# DC_DC_5V_2.net
KiCad netlist of a schematic drawn in Altium Designer
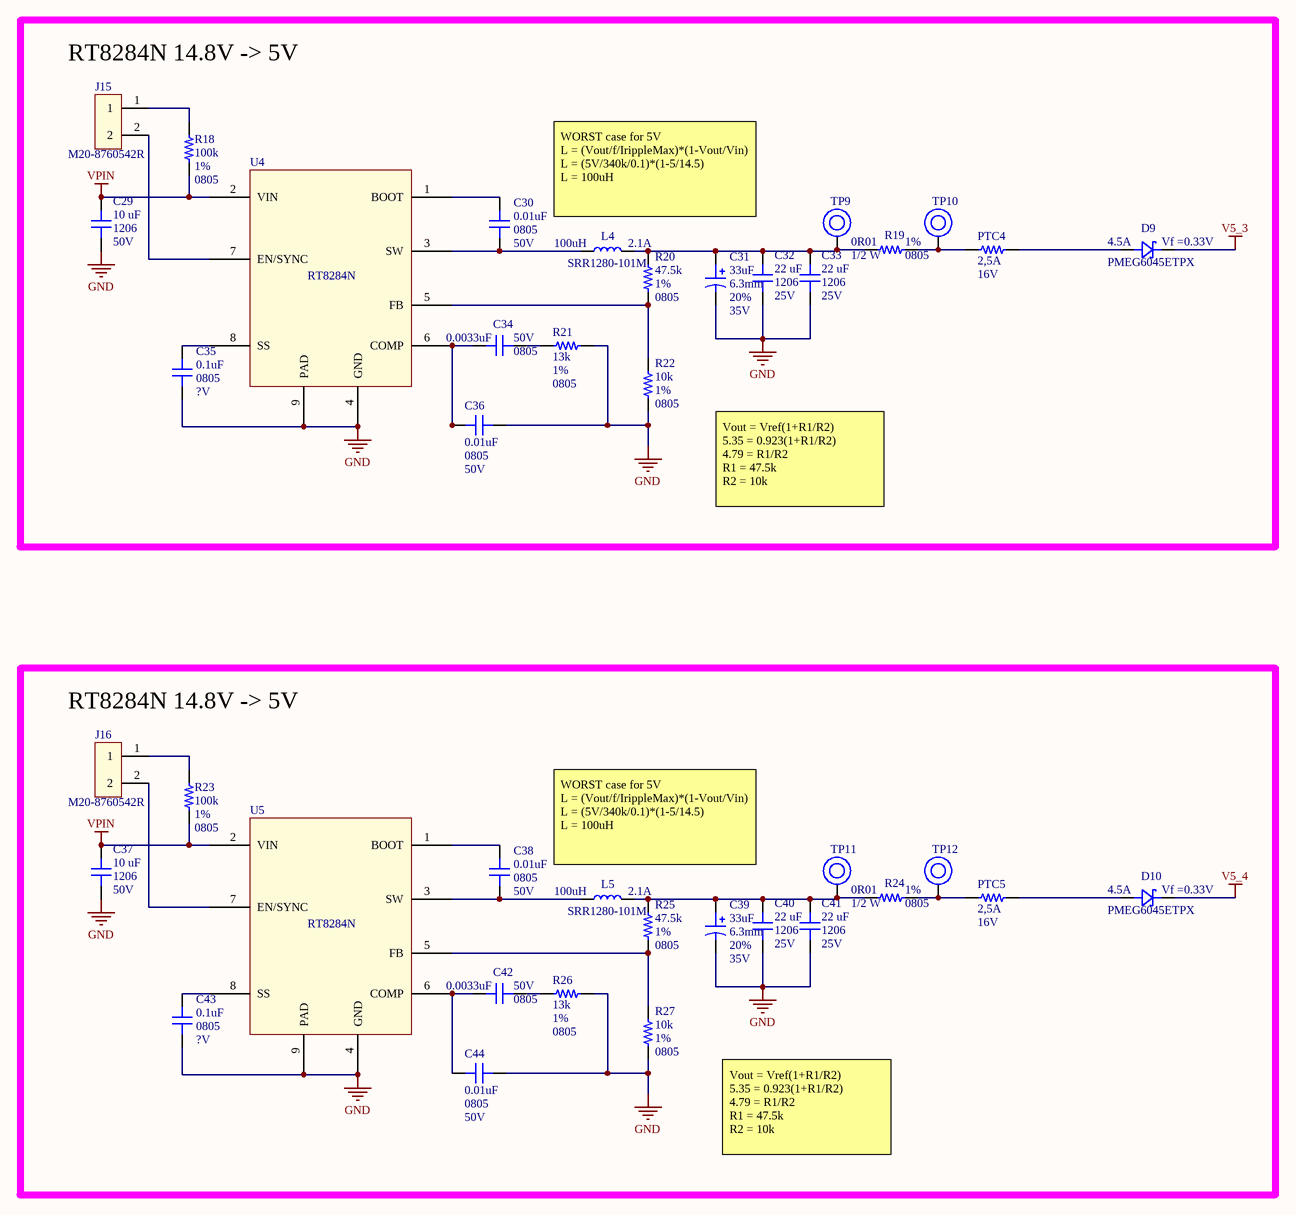
[diagram p0: DC_DC_5V_2.SchDoc]

(export (version "E")
  (design (tool "Eeschema 10.0.6"))
  (components
    (comp (ref "C29")
      (value "10 uF")
      (footprint "CAP_1206")
      (description "CAP - 1206")
      (fields
        (field (name "PACKAGE") "1206")
        (field (name "VOLTAGE") "50V")
        (field (name "PART NUMBER") "GRT31CR61H106ME01L")
      )
      (libsource (lib "SecureBot") (part "CAP - 1206"))
    )
    (comp (ref "C30")
      (value "0.01uF")
      (footprint "CAP_0805")
      (description "CAP - 0805")
      (fields
        (field (name "PART NUMBER") "CL21B103KBANNNC")
        (field (name "PACKAGE") "0805")
        (field (name "VOLTAGE") "50V")
      )
      (libsource (lib "SecureBot") (part "CAP - 0805"))
    )
    (comp (ref "C31")
      (value "33uF")
      (footprint "CAP ALU - 6.3mm DIA")
      (description "CAP ALU - 6.3mm")
      (fields
        (field (name "PACKAGE") "6.3mm")
        (field (name "TOLERANCE") "20%")
        (field (name "VOLTAGE") "35V")
        (field (name "PART NUMBER") "EEE-FK1V330P")
      )
      (libsource (lib "SecureBot") (part "CAP ALU - 6_3mm"))
    )
    (comp (ref "C32")
      (value "22 uF")
      (footprint "CAP_1206")
      (description "CAP - 1206")
      (fields
        (field (name "PACKAGE") "1206")
        (field (name "VOLTAGE") "25V")
        (field (name "PART NUMBER") "CL31A226KAHNNNE")
      )
      (libsource (lib "SecureBot") (part "CAP - 1206"))
    )
    (comp (ref "C33")
      (value "22 uF")
      (footprint "CAP_1206")
      (description "CAP - 1206")
      (fields
        (field (name "PACKAGE") "1206")
        (field (name "VOLTAGE") "25V")
        (field (name "PART NUMBER") "CL31A226KAHNNNE")
      )
      (libsource (lib "SecureBot") (part "CAP - 1206"))
    )
    (comp (ref "C34")
      (value "0.0033uF")
      (footprint "CAP_0805")
      (description "CAP - 0805")
      (fields
        (field (name "PART NUMBER") "CL21B332KBANNNC")
        (field (name "PACKAGE") "0805")
        (field (name "VOLTAGE") "50V")
      )
      (libsource (lib "SecureBot") (part "CAP - 0805"))
    )
    (comp (ref "C35")
      (value "0.1uF")
      (footprint "CAP_0805")
      (description "CAP - 0805")
      (fields
        (field (name "PART NUMBER") "CC0805KRX7R9BB104")
        (field (name "PACKAGE") "0805")
        (field (name "VOLTAGE") "?V")
      )
      (libsource (lib "SecureBot") (part "CAP - 0805"))
    )
    (comp (ref "C36")
      (value "0.01uF")
      (footprint "CAP_0805")
      (description "CAP - 0805")
      (fields
        (field (name "PART NUMBER") "CL21B103KBANNNC")
        (field (name "PACKAGE") "0805")
        (field (name "VOLTAGE") "50V")
      )
      (libsource (lib "SecureBot") (part "CAP - 0805"))
    )
    (comp (ref "C37")
      (value "10 uF")
      (footprint "CAP_1206")
      (description "CAP - 1206")
      (fields
        (field (name "PACKAGE") "1206")
        (field (name "VOLTAGE") "50V")
        (field (name "PART NUMBER") "GRT31CR61H106ME01L")
      )
      (libsource (lib "SecureBot") (part "CAP - 1206"))
    )
    (comp (ref "C38")
      (value "0.01uF")
      (footprint "CAP_0805")
      (description "CAP - 0805")
      (fields
        (field (name "PART NUMBER") "CL21B103KBANNNC")
        (field (name "PACKAGE") "0805")
        (field (name "VOLTAGE") "50V")
      )
      (libsource (lib "SecureBot") (part "CAP - 0805"))
    )
    (comp (ref "C39")
      (value "33uF")
      (footprint "CAP ALU - 6.3mm DIA")
      (description "CAP ALU - 6.3mm")
      (fields
        (field (name "PACKAGE") "6.3mm")
        (field (name "TOLERANCE") "20%")
        (field (name "VOLTAGE") "35V")
        (field (name "PART NUMBER") "EEE-FK1V330P")
      )
      (libsource (lib "SecureBot") (part "CAP ALU - 6_3mm"))
    )
    (comp (ref "C40")
      (value "22 uF")
      (footprint "CAP_1206")
      (description "CAP - 1206")
      (fields
        (field (name "PACKAGE") "1206")
        (field (name "VOLTAGE") "25V")
        (field (name "PART NUMBER") "CL31A226KAHNNNE")
      )
      (libsource (lib "SecureBot") (part "CAP - 1206"))
    )
    (comp (ref "C41")
      (value "22 uF")
      (footprint "CAP_1206")
      (description "CAP - 1206")
      (fields
        (field (name "PACKAGE") "1206")
        (field (name "VOLTAGE") "25V")
        (field (name "PART NUMBER") "CL31A226KAHNNNE")
      )
      (libsource (lib "SecureBot") (part "CAP - 1206"))
    )
    (comp (ref "C42")
      (value "0.0033uF")
      (footprint "CAP_0805")
      (description "CAP - 0805")
      (fields
        (field (name "PART NUMBER") "CL21B332KBANNNC")
        (field (name "PACKAGE") "0805")
        (field (name "VOLTAGE") "50V")
      )
      (libsource (lib "SecureBot") (part "CAP - 0805"))
    )
    (comp (ref "C43")
      (value "0.1uF")
      (footprint "CAP_0805")
      (description "CAP - 0805")
      (fields
        (field (name "PART NUMBER") "CC0805KRX7R9BB104")
        (field (name "PACKAGE") "0805")
        (field (name "VOLTAGE") "?V")
      )
      (libsource (lib "SecureBot") (part "CAP - 0805"))
    )
    (comp (ref "C44")
      (value "0.01uF")
      (footprint "CAP_0805")
      (description "CAP - 0805")
      (fields
        (field (name "PART NUMBER") "CL21B103KBANNNC")
        (field (name "PACKAGE") "0805")
        (field (name "VOLTAGE") "50V")
      )
      (libsource (lib "SecureBot") (part "CAP - 0805"))
    )
    (comp (ref "D9")
      (value "SCHOTTKEY")
      (footprint "DO-214AC_SOD128")
      (fields
        (field (name "CURRENT") "4.5A")
        (field (name "VF") "Vf =0.33V")
        (field (name "PART NUMBER") "PMEG6045ETPX")
      )
      (libsource (lib "SecureBot") (part "SCHOTTKEY"))
    )
    (comp (ref "D10")
      (value "SCHOTTKEY")
      (footprint "DO-214AC_SOD128")
      (fields
        (field (name "CURRENT") "4.5A")
        (field (name "VF") "Vf =0.33V")
        (field (name "PART NUMBER") "PMEG6045ETPX")
      )
      (libsource (lib "SecureBot") (part "SCHOTTKEY"))
    )
    (comp (ref "J15")
      (value "Header 2 pin SM")
      (footprint "HDR1X2")
      (fields (field (name "PART NUMBER") "M20-8760542R"))
      (libsource (lib "SecureBot") (part "Header 2 pin SM"))
    )
    (comp (ref "J16")
      (value "Header 2 pin SM")
      (footprint "HDR1X2")
      (fields (field (name "PART NUMBER") "M20-8760542R"))
      (libsource (lib "SecureBot") (part "Header 2 pin SM"))
    )
    (comp (ref "L4")
      (value "100uH")
      (footprint "BOURNS 12.5x12.5mm")
      (description "IND")
      (fields (field (name "CURRENT") "2.1A") (field (name "PART NUMBER") "SRR1280-101M"))
      (libsource (lib "SecureBot") (part "IND"))
    )
    (comp (ref "L5")
      (value "100uH")
      (footprint "BOURNS 12.5x12.5mm")
      (description "IND")
      (fields (field (name "CURRENT") "2.1A") (field (name "PART NUMBER") "SRR1280-101M"))
      (libsource (lib "SecureBot") (part "IND"))
    )
    (comp (ref "PTC4")
      (value "PTC - 1812")
      (footprint "PTC - 1812")
      (fields
        (field (name "PART NUMBER") "0ZCG0160BF2C")
        (field (name "TRIP VALUE") "2,5A")
        (field (name "VOLTAGE") "16V")
      )
      (libsource (lib "SecureBot") (part "PTC - 1812"))
    )
    (comp (ref "PTC5")
      (value "PTC - 1812")
      (footprint "PTC - 1812")
      (fields
        (field (name "PART NUMBER") "0ZCG0160BF2C")
        (field (name "TRIP VALUE") "2,5A")
        (field (name "VOLTAGE") "16V")
      )
      (libsource (lib "SecureBot") (part "PTC - 1812"))
    )
    (comp (ref "R18")
      (value "100k")
      (footprint "FER_0805")
      (description "RES - 0805")
      (fields
        (field (name "TOLERANCE") "1%")
        (field (name "PACKAGE") "0805")
        (field (name "PART NUMBER") "RMCF0805FT100K")
      )
      (libsource (lib "SecureBot") (part "RES - 0805"))
    )
    (comp (ref "R19")
      (value "0R01")
      (footprint "FER_0805")
      (description "RES - 0805")
      (fields
        (field (name "WATT") "1/2 W")
        (field (name "TOLERANCE") "1%")
        (field (name "PACKAGE") "0805")
        (field (name "PART NUMBER") "KRL1220E-M-R010-F-T5")
      )
      (libsource (lib "SecureBot") (part "RES - 0805"))
    )
    (comp (ref "R20")
      (value "47.5k")
      (footprint "FER_0805")
      (description "RES - 0805")
      (fields
        (field (name "TOLERANCE") "1%")
        (field (name "PACKAGE") "0805")
        (field (name "PART NUMBER") "RMCF0805FT47K5")
      )
      (libsource (lib "SecureBot") (part "RES - 0805"))
    )
    (comp (ref "R21")
      (value "13k")
      (footprint "FER_0805")
      (description "RES - 0805")
      (fields
        (field (name "TOLERANCE") "1%")
        (field (name "PACKAGE") "0805")
        (field (name "PART NUMBER") "RC0805FR-0713KL")
      )
      (libsource (lib "SecureBot") (part "RES - 0805"))
    )
    (comp (ref "R22")
      (value "10k")
      (footprint "FER_0805")
      (description "RES - 0805")
      (fields
        (field (name "TOLERANCE") "1%")
        (field (name "PACKAGE") "0805")
        (field (name "PART NUMBER") "RMCF0805FT10K0")
      )
      (libsource (lib "SecureBot") (part "RES - 0805"))
    )
    (comp (ref "R23")
      (value "100k")
      (footprint "FER_0805")
      (description "RES - 0805")
      (fields
        (field (name "TOLERANCE") "1%")
        (field (name "PACKAGE") "0805")
        (field (name "PART NUMBER") "RMCF0805FT100K")
      )
      (libsource (lib "SecureBot") (part "RES - 0805"))
    )
    (comp (ref "R24")
      (value "0R01")
      (footprint "FER_0805")
      (description "RES - 0805")
      (fields
        (field (name "WATT") "1/2 W")
        (field (name "TOLERANCE") "1%")
        (field (name "PACKAGE") "0805")
        (field (name "PART NUMBER") "KRL1220E-M-R010-F-T5")
      )
      (libsource (lib "SecureBot") (part "RES - 0805"))
    )
    (comp (ref "R25")
      (value "47.5k")
      (footprint "FER_0805")
      (description "RES - 0805")
      (fields
        (field (name "TOLERANCE") "1%")
        (field (name "PACKAGE") "0805")
        (field (name "PART NUMBER") "RMCF0805FT47K5")
      )
      (libsource (lib "SecureBot") (part "RES - 0805"))
    )
    (comp (ref "R26")
      (value "13k")
      (footprint "FER_0805")
      (description "RES - 0805")
      (fields
        (field (name "TOLERANCE") "1%")
        (field (name "PACKAGE") "0805")
        (field (name "PART NUMBER") "RC0805FR-0713KL")
      )
      (libsource (lib "SecureBot") (part "RES - 0805"))
    )
    (comp (ref "R27")
      (value "10k")
      (footprint "FER_0805")
      (description "RES - 0805")
      (fields
        (field (name "TOLERANCE") "1%")
        (field (name "PACKAGE") "0805")
        (field (name "PART NUMBER") "RMCF0805FT10K0")
      )
      (libsource (lib "SecureBot") (part "RES - 0805"))
    )
    (comp (ref "TP9")
      (value "TestPoint 3x3mm")
      (footprint "TestPoint 3X3mm")
      (libsource (lib "SecureBot") (part "TestPoint 3x3mm"))
    )
    (comp (ref "TP10")
      (value "TestPoint 3x3mm")
      (footprint "TestPoint 3X3mm")
      (libsource (lib "SecureBot") (part "TestPoint 3x3mm"))
    )
    (comp (ref "TP11")
      (value "TestPoint 3x3mm")
      (footprint "TestPoint 3X3mm")
      (libsource (lib "SecureBot") (part "TestPoint 3x3mm"))
    )
    (comp (ref "TP12")
      (value "TestPoint 3x3mm")
      (footprint "TestPoint 3X3mm")
      (libsource (lib "SecureBot") (part "TestPoint 3x3mm"))
    )
    (comp (ref "U4") (value "RT8284N") (footprint "SOP8") (libsource (lib "SecureBot") (part "RT8284N")))
    (comp (ref "U5") (value "RT8284N") (footprint "SOP8") (libsource (lib "SecureBot") (part "RT8284N")))
  )
  (nets
    (net (code "1") (name "GND") (class "Default")
      (node (ref "C29") (pin "2") (pinfunction "2_2") (pintype "passive"))
      (node (ref "C31") (pin "2") (pinfunction "2_2") (pintype "passive"))
      (node (ref "C32") (pin "2") (pinfunction "2_2") (pintype "passive"))
      (node (ref "C33") (pin "2") (pinfunction "2_2") (pintype "passive"))
      (node (ref "C35") (pin "2") (pinfunction "2_2") (pintype "passive"))
      (node (ref "C36") (pin "2") (pinfunction "2_2") (pintype "passive"))
      (node (ref "C37") (pin "2") (pinfunction "2_2") (pintype "passive"))
      (node (ref "C39") (pin "2") (pinfunction "2_2") (pintype "passive"))
      (node (ref "C40") (pin "2") (pinfunction "2_2") (pintype "passive"))
      (node (ref "C41") (pin "2") (pinfunction "2_2") (pintype "passive"))
      (node (ref "C43") (pin "2") (pinfunction "2_2") (pintype "passive"))
      (node (ref "C44") (pin "2") (pinfunction "2_2") (pintype "passive"))
      (node (ref "R21") (pin "2") (pinfunction "2_2") (pintype "passive"))
      (node (ref "R22") (pin "2") (pinfunction "2_2") (pintype "passive"))
      (node (ref "R26") (pin "2") (pinfunction "2_2") (pintype "passive"))
      (node (ref "R27") (pin "2") (pinfunction "2_2") (pintype "passive"))
      (node (ref "U4") (pin "4") (pinfunction "GND_4") (pintype "passive"))
      (node (ref "U4") (pin "9") (pinfunction "PAD_9") (pintype "passive"))
      (node (ref "U5") (pin "4") (pinfunction "GND_4") (pintype "passive"))
      (node (ref "U5") (pin "9") (pinfunction "PAD_9") (pintype "passive"))
    )
    (net (code "2") (name "Net-(C31-Pad1)") (class "Default")
      (node (ref "C31") (pin "1") (pinfunction "1_1") (pintype "passive"))
      (node (ref "C32") (pin "1") (pinfunction "1_1") (pintype "passive"))
      (node (ref "C33") (pin "1") (pinfunction "1_1") (pintype "passive"))
      (node (ref "L4") (pin "2") (pinfunction "2_2") (pintype "passive"))
      (node (ref "R19") (pin "1") (pinfunction "1_1") (pintype "passive"))
      (node (ref "R20") (pin "1") (pinfunction "1_1") (pintype "passive"))
      (node (ref "TP9") (pin "1") (pinfunction "1_1") (pintype "passive"))
    )
    (net (code "3") (name "Net-(C34-Pad2)") (class "Default")
      (node (ref "C34") (pin "2") (pinfunction "2_2") (pintype "passive"))
      (node (ref "R21") (pin "1") (pinfunction "1_1") (pintype "passive"))
    )
    (net (code "4") (name "Net-(C39-Pad1)") (class "Default")
      (node (ref "C39") (pin "1") (pinfunction "1_1") (pintype "passive"))
      (node (ref "C40") (pin "1") (pinfunction "1_1") (pintype "passive"))
      (node (ref "C41") (pin "1") (pinfunction "1_1") (pintype "passive"))
      (node (ref "L5") (pin "2") (pinfunction "2_2") (pintype "passive"))
      (node (ref "R24") (pin "1") (pinfunction "1_1") (pintype "passive"))
      (node (ref "R25") (pin "1") (pinfunction "1_1") (pintype "passive"))
      (node (ref "TP11") (pin "1") (pinfunction "1_1") (pintype "passive"))
    )
    (net (code "5") (name "Net-(C42-Pad2)") (class "Default")
      (node (ref "C42") (pin "2") (pinfunction "2_2") (pintype "passive"))
      (node (ref "R26") (pin "1") (pinfunction "1_1") (pintype "passive"))
    )
    (net (code "6") (name "Net-(D9-Pad1)") (class "Default")
      (node (ref "D9") (pin "1") (pinfunction "1_1") (pintype "passive"))
      (node (ref "PTC4") (pin "2") (pinfunction "2_2") (pintype "passive"))
    )
    (net (code "7") (name "Net-(D10-Pad1)") (class "Default")
      (node (ref "D10") (pin "1") (pinfunction "1_1") (pintype "passive"))
      (node (ref "PTC5") (pin "2") (pinfunction "2_2") (pintype "passive"))
    )
    (net (code "8") (name "Net-(J15-Pad1)") (class "Default")
      (node (ref "J15") (pin "1") (pinfunction "1_1") (pintype "passive"))
      (node (ref "R18") (pin "2") (pinfunction "2_2") (pintype "passive"))
    )
    (net (code "9") (name "Net-(J16-Pad1)") (class "Default")
      (node (ref "J16") (pin "1") (pinfunction "1_1") (pintype "passive"))
      (node (ref "R23") (pin "2") (pinfunction "2_2") (pintype "passive"))
    )
    (net (code "10") (name "Net-(PTC4-Pad1)") (class "Default")
      (node (ref "PTC4") (pin "1") (pinfunction "1_1") (pintype "passive"))
      (node (ref "R19") (pin "2") (pinfunction "2_2") (pintype "passive"))
      (node (ref "TP10") (pin "1") (pinfunction "1_1") (pintype "passive"))
    )
    (net (code "11") (name "Net-(PTC5-Pad1)") (class "Default")
      (node (ref "PTC5") (pin "1") (pinfunction "1_1") (pintype "passive"))
      (node (ref "R24") (pin "2") (pinfunction "2_2") (pintype "passive"))
      (node (ref "TP12") (pin "1") (pinfunction "1_1") (pintype "passive"))
    )
    (net (code "12") (name "Net-(U4-BOOT)") (class "Default")
      (node (ref "C30") (pin "1") (pinfunction "1_1") (pintype "passive"))
      (node (ref "U4") (pin "1") (pinfunction "BOOT_1") (pintype "passive"))
    )
    (net (code "13") (name "Net-(U4-COMP)") (class "Default")
      (node (ref "C34") (pin "1") (pinfunction "1_1") (pintype "passive"))
      (node (ref "C36") (pin "1") (pinfunction "1_1") (pintype "passive"))
      (node (ref "U4") (pin "6") (pinfunction "COMP_6") (pintype "passive"))
    )
    (net (code "14") (name "Net-(U4-EN{slash}SYNC)") (class "Default")
      (node (ref "J15") (pin "2") (pinfunction "2_2") (pintype "passive"))
      (node (ref "U4") (pin "7") (pinfunction "EN/SYNC_7") (pintype "passive"))
    )
    (net (code "15") (name "Net-(U4-FB)") (class "Default")
      (node (ref "R20") (pin "2") (pinfunction "2_2") (pintype "passive"))
      (node (ref "R22") (pin "1") (pinfunction "1_1") (pintype "passive"))
      (node (ref "U4") (pin "5") (pinfunction "FB_5") (pintype "passive"))
    )
    (net (code "16") (name "Net-(U4-SS)") (class "Default")
      (node (ref "C35") (pin "1") (pinfunction "1_1") (pintype "passive"))
      (node (ref "U4") (pin "8") (pinfunction "SS_8") (pintype "passive"))
    )
    (net (code "17") (name "Net-(U4-SW)") (class "Default")
      (node (ref "C30") (pin "2") (pinfunction "2_2") (pintype "passive"))
      (node (ref "L4") (pin "1") (pinfunction "1_1") (pintype "passive"))
      (node (ref "U4") (pin "3") (pinfunction "SW_3") (pintype "passive"))
    )
    (net (code "18") (name "Net-(U5-BOOT)") (class "Default")
      (node (ref "C38") (pin "1") (pinfunction "1_1") (pintype "passive"))
      (node (ref "U5") (pin "1") (pinfunction "BOOT_1") (pintype "passive"))
    )
    (net (code "19") (name "Net-(U5-COMP)") (class "Default")
      (node (ref "C42") (pin "1") (pinfunction "1_1") (pintype "passive"))
      (node (ref "C44") (pin "1") (pinfunction "1_1") (pintype "passive"))
      (node (ref "U5") (pin "6") (pinfunction "COMP_6") (pintype "passive"))
    )
    (net (code "20") (name "Net-(U5-EN{slash}SYNC)") (class "Default")
      (node (ref "J16") (pin "2") (pinfunction "2_2") (pintype "passive"))
      (node (ref "U5") (pin "7") (pinfunction "EN/SYNC_7") (pintype "passive"))
    )
    (net (code "21") (name "Net-(U5-FB)") (class "Default")
      (node (ref "R25") (pin "2") (pinfunction "2_2") (pintype "passive"))
      (node (ref "R27") (pin "1") (pinfunction "1_1") (pintype "passive"))
      (node (ref "U5") (pin "5") (pinfunction "FB_5") (pintype "passive"))
    )
    (net (code "22") (name "Net-(U5-SS)") (class "Default")
      (node (ref "C43") (pin "1") (pinfunction "1_1") (pintype "passive"))
      (node (ref "U5") (pin "8") (pinfunction "SS_8") (pintype "passive"))
    )
    (net (code "23") (name "Net-(U5-SW)") (class "Default")
      (node (ref "C38") (pin "2") (pinfunction "2_2") (pintype "passive"))
      (node (ref "L5") (pin "1") (pinfunction "1_1") (pintype "passive"))
      (node (ref "U5") (pin "3") (pinfunction "SW_3") (pintype "passive"))
    )
    (net (code "24") (name "V5_3") (class "Default")
      (node (ref "D9") (pin "2") (pinfunction "2_2") (pintype "passive"))
    )
    (net (code "25") (name "V5_4") (class "Default")
      (node (ref "D10") (pin "2") (pinfunction "2_2") (pintype "passive"))
    )
    (net (code "26") (name "VPIN") (class "Default")
      (node (ref "C29") (pin "1") (pinfunction "1_1") (pintype "passive"))
      (node (ref "C37") (pin "1") (pinfunction "1_1") (pintype "passive"))
      (node (ref "R18") (pin "1") (pinfunction "1_1") (pintype "passive"))
      (node (ref "R23") (pin "1") (pinfunction "1_1") (pintype "passive"))
      (node (ref "U4") (pin "2") (pinfunction "VIN_2") (pintype "passive"))
      (node (ref "U5") (pin "2") (pinfunction "VIN_2") (pintype "passive"))
    )
  )
)
